# os31_master.net
KiCad netlist of a schematic drawn in EAGLE
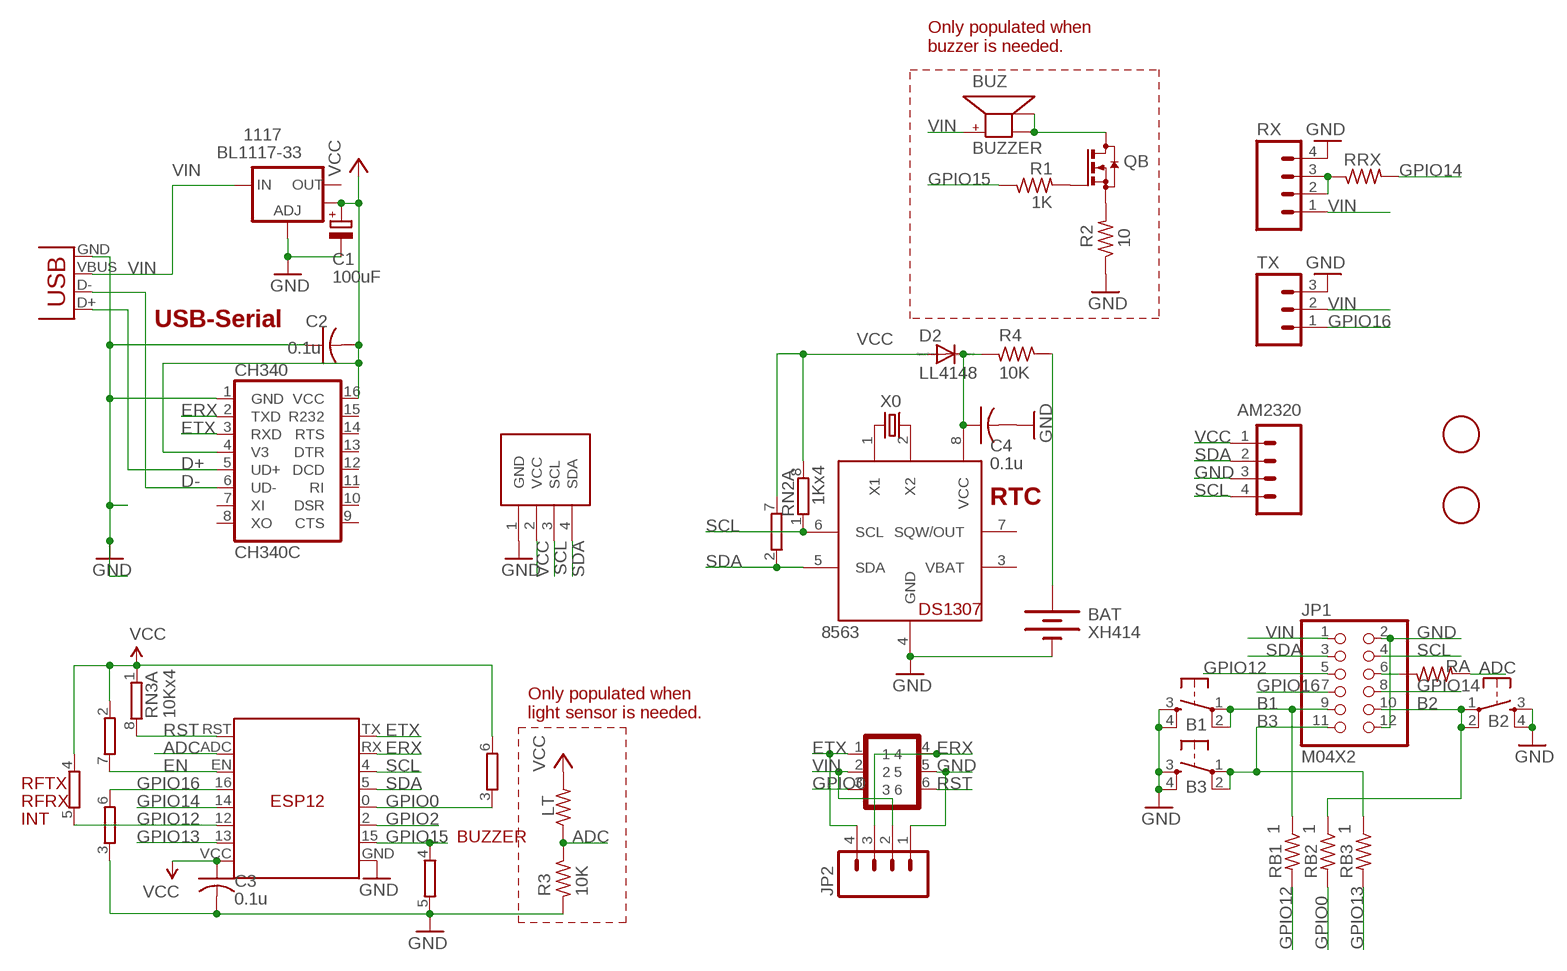
[diagram p0: schematic, sheet 1]

(export (version "E")
  (design (tool "Eeschema 10.0.6"))
  (components
    (comp (ref "1F")
      (value "FIDUCIAL")
      (footprint "eagle-import:FIDUCIAL_1MM")
      (libsource (lib "eagle-import") (part "FIDUCIAL"))
    )
    (comp (ref "2F")
      (value "FIDUCIAL")
      (footprint "eagle-import:FIDUCIAL_1MM")
      (libsource (lib "eagle-import") (part "FIDUCIAL"))
    )
    (comp (ref "1117")
      (value "BL1117-33")
      (footprint "eagle-import:SOT223")
      (libsource (lib "eagle-import") (part "V_REG_LM1117SOT223"))
    )
    (comp (ref "8563")
      (value "PCF8563")
      (footprint "eagle-import:SO08")
      (libsource (lib "eagle-import") (part "DS1307SOIC"))
    )
    (comp (ref "AM2320")
      (value "M04NARROW")
      (footprint "eagle-import:1X04-NARROW")
      (libsource (lib "eagle-import") (part "M04NARROW"))
    )
    (comp (ref "B1")
      (value "SPST_TACTEVQQ2")
      (footprint "eagle-import:EVQ-Q2")
      (libsource (lib "eagle-import") (part "SPST_TACTEVQQ2"))
    )
    (comp (ref "B2")
      (value "SPST_TACTEVQQ2")
      (footprint "eagle-import:EVQ-Q2")
      (libsource (lib "eagle-import") (part "SPST_TACTEVQQ2"))
    )
    (comp (ref "B3")
      (value "SPST_TACTEVQQ2")
      (footprint "eagle-import:EVQ-Q2")
      (libsource (lib "eagle-import") (part "SPST_TACTEVQQ2"))
    )
    (comp (ref "BAT")
      (value "XH414")
      (footprint "eagle-import:BATTCON_XH414")
      (libsource (lib "eagle-import") (part "BATTERYXH414"))
    )
    (comp (ref "BUZ")
      (value "BUZZER")
      (footprint "eagle-import:SMT-8585-BUZZER")
      (libsource (lib "eagle-import") (part "BUZZER"))
    )
    (comp (ref "C1")
      (value "100uF")
      (footprint "eagle-import:CT3528")
      (libsource (lib "eagle-import") (part "CPOL-EUCT3528"))
    )
    (comp (ref "C2")
      (value "0.1u")
      (footprint "eagle-import:C0603")
      (libsource (lib "eagle-import") (part "C-USC0603"))
    )
    (comp (ref "C3")
      (value "0.1u")
      (footprint "eagle-import:C0603")
      (libsource (lib "eagle-import") (part "C-USC0603"))
    )
    (comp (ref "C4")
      (value "0.1u")
      (footprint "eagle-import:C0603")
      (libsource (lib "eagle-import") (part "C-USC0603"))
    )
    (comp (ref "CH340")
      (value "CH340C")
      (footprint "eagle-import:SO16")
      (libsource (lib "eagle-import") (part "CH340G"))
    )
    (comp (ref "D2")
      (value "LL4148")
      (footprint "eagle-import:SOD123")
      (libsource (lib "eagle-import") (part "DIODE-SOD123"))
    )
    (comp (ref "ESP")
      (value "ESP-12N")
      (footprint "eagle-import:ESP12_WES")
      (libsource (lib "eagle-import") (part "ESP12ESPWES"))
    )
    (comp (ref "JP1")
      (value "M04X2")
      (footprint "eagle-import:2X06")
      (libsource (lib "eagle-import") (part "PINHD-2X6"))
    )
    (comp (ref "JP2")
      (value "M04PTH")
      (footprint "eagle-import:1X04")
      (libsource (lib "eagle-import") (part "SparkFunNew_M04PTH"))
    )
    (comp (ref "LCD")
      (value "SSD1306_OLED_I2CSMD3")
      (footprint "eagle-import:SSD1306_OLED_I2C_SMD3")
      (libsource (lib "eagle-import") (part "SSD1306_OLED_I2CSMD3"))
    )
    (comp (ref "LT")
      (value "100K")
      (footprint "eagle-import:R1206")
      (libsource (lib "eagle-import") (part "R-US_R1206"))
    )
    (comp (ref "QB")
      (value "MMBT3904")
      (footprint "eagle-import:SOT23")
      (libsource (lib "eagle-import") (part "BSS123"))
    )
    (comp (ref "R1")
      (value "1K")
      (footprint "eagle-import:R0603")
      (libsource (lib "eagle-import") (part "adafruitGood_R-US_R0603"))
    )
    (comp (ref "R2")
      (value "10")
      (footprint "eagle-import:R0603")
      (libsource (lib "eagle-import") (part "adafruitGood_R-US_R0603"))
    )
    (comp (ref "R3")
      (value "10K")
      (footprint "eagle-import:R0603")
      (libsource (lib "eagle-import") (part "adafruitGood_R-US_R0603"))
    )
    (comp (ref "R4")
      (value "10K")
      (footprint "eagle-import:R0603")
      (libsource (lib "eagle-import") (part "adafruitGood_R-US_R0603"))
    )
    (comp (ref "RA")
      (value "1")
      (footprint "eagle-import:R0603")
      (libsource (lib "eagle-import") (part "adafruitGood_R-US_R0603"))
    )
    (comp (ref "RB1")
      (value "1")
      (footprint "eagle-import:R0603")
      (libsource (lib "eagle-import") (part "R-US_R0603"))
    )
    (comp (ref "RB2")
      (value "1")
      (footprint "eagle-import:R0603")
      (libsource (lib "eagle-import") (part "R-US_R0603"))
    )
    (comp (ref "RB3")
      (value "1")
      (footprint "eagle-import:R0603")
      (libsource (lib "eagle-import") (part "R-US_R0603"))
    )
    (comp (ref "RN2")
      (value "1Kx4")
      (footprint "eagle-import:EXB38V")
      (libsource (lib "eagle-import") (part "4R-NEXB38V"))
    )
    (comp (ref "RN3")
      (value "10Kx4")
      (footprint "eagle-import:EXB38V")
      (libsource (lib "eagle-import") (part "4R-NEXB38V"))
    )
    (comp (ref "RRX")
      (value "1K")
      (footprint "eagle-import:R0603")
      (libsource (lib "eagle-import") (part "adafruitGood_R-US_R0603"))
    )
    (comp (ref "RX")
      (value "M04LOCK")
      (footprint "eagle-import:1X04_LOCK")
      (libsource (lib "eagle-import") (part "M04LOCK"))
    )
    (comp (ref "TX")
      (value "M03LOCK")
      (footprint "eagle-import:1X03_LOCK")
      (libsource (lib "eagle-import") (part "M03LOCK"))
    )
    (comp (ref "U$3")
      (value "GOLDFINGER_2X3")
      (footprint "eagle-import:GOLDFINGER_2X3")
      (libsource (lib "eagle-import") (part "GOLDFINGER_2X3"))
    )
    (comp (ref "USB")
      (value "USBMICROB2")
      (footprint "eagle-import:USB-MICROB2")
      (libsource (lib "eagle-import") (part "USBMICROB2"))
    )
    (comp (ref "X0")
      (value "32.768kHz")
      (footprint "eagle-import:MM20SS1")
      (libsource (lib "eagle-import") (part "CRYSTALMM20SS1"))
    )
  )
  (nets
    (net (code "1") (name "/ADC") (class "Default")
      (node (ref "ESP") (pin "ADC") (pinfunction "ADC_ADC") (pintype "bidirectional"))
      (node (ref "LT") (pin "1") (pinfunction "1_1") (pintype "passive"))
      (node (ref "R3") (pin "1") (pinfunction "1_1") (pintype "passive"))
      (node (ref "RA") (pin "2") (pinfunction "2_2") (pintype "passive"))
    )
    (net (code "2") (name "/B1") (class "Default")
      (node (ref "B1") (pin "1") (pinfunction "1_1") (pintype "passive"))
      (node (ref "B1") (pin "2") (pinfunction "2_2") (pintype "passive"))
      (node (ref "JP1") (pin "9") (pinfunction "9_9") (pintype "passive"))
      (node (ref "RB1") (pin "1") (pinfunction "1_1") (pintype "passive"))
    )
    (net (code "3") (name "/B2") (class "Default")
      (node (ref "B2") (pin "1") (pinfunction "1_1") (pintype "passive"))
      (node (ref "B2") (pin "2") (pinfunction "2_2") (pintype "passive"))
      (node (ref "JP1") (pin "10") (pinfunction "10_10") (pintype "passive"))
      (node (ref "RB2") (pin "1") (pinfunction "1_1") (pintype "passive"))
    )
    (net (code "4") (name "/B3") (class "Default")
      (node (ref "B3") (pin "1") (pinfunction "1_1") (pintype "passive"))
      (node (ref "B3") (pin "2") (pinfunction "2_2") (pintype "passive"))
      (node (ref "JP1") (pin "11") (pinfunction "11_11") (pintype "passive"))
      (node (ref "RB3") (pin "1") (pinfunction "1_1") (pintype "passive"))
    )
    (net (code "5") (name "/D+") (class "Default")
      (node (ref "CH340") (pin "5") (pinfunction "UD+_5") (pintype "bidirectional"))
      (node (ref "USB") (pin "D+") (pinfunction "D+_D+") (pintype "bidirectional"))
    )
    (net (code "6") (name "/D-") (class "Default")
      (node (ref "CH340") (pin "6") (pinfunction "UD-_6") (pintype "bidirectional"))
      (node (ref "USB") (pin "D-") (pinfunction "D-_D-") (pintype "bidirectional"))
    )
    (net (code "7") (name "/EN") (class "Default")
      (node (ref "ESP") (pin "EN") (pinfunction "EN_EN") (pintype "bidirectional"))
      (node (ref "RN3") (pin "7") (pinfunction "2_7") (pintype "passive"))
    )
    (net (code "8") (name "/ERX") (class "Default")
      (node (ref "CH340") (pin "2") (pinfunction "TXD_2") (pintype "bidirectional"))
      (node (ref "ESP") (pin "RX") (pinfunction "RX_RX") (pintype "bidirectional"))
      (node (ref "JP2") (pin "3") (pinfunction "3_3") (pintype "passive"))
      (node (ref "U$3") (pin "4") (pinfunction "4_4") (pintype "bidirectional"))
    )
    (net (code "9") (name "/ETX") (class "Default")
      (node (ref "CH340") (pin "3") (pinfunction "RXD_3") (pintype "bidirectional"))
      (node (ref "ESP") (pin "TX") (pinfunction "TX_TX") (pintype "bidirectional"))
      (node (ref "JP2") (pin "4") (pinfunction "4_4") (pintype "passive"))
      (node (ref "U$3") (pin "1") (pinfunction "1_1") (pintype "bidirectional"))
    )
    (net (code "10") (name "/GPIO0") (class "Default")
      (node (ref "ESP") (pin "0") (pinfunction "G0_0") (pintype "bidirectional"))
      (node (ref "RB2") (pin "2") (pinfunction "2_2") (pintype "passive"))
      (node (ref "RN2") (pin "3") (pinfunction "1_3") (pintype "passive"))
      (node (ref "U$3") (pin "3") (pinfunction "3_3") (pintype "bidirectional"))
    )
    (net (code "11") (name "/GPIO2") (class "Default")
      (node (ref "ESP") (pin "2") (pinfunction "G2_2") (pintype "bidirectional"))
    )
    (net (code "12") (name "/GPIO12") (class "Default")
      (node (ref "ESP") (pin "12") (pinfunction "G12_12") (pintype "bidirectional"))
      (node (ref "JP1") (pin "5") (pinfunction "5_5") (pintype "passive"))
      (node (ref "RB1") (pin "2") (pinfunction "2_2") (pintype "passive"))
      (node (ref "RN3") (pin "5") (pinfunction "2_5") (pintype "passive"))
    )
    (net (code "13") (name "/GPIO13") (class "Default")
      (node (ref "ESP") (pin "13") (pinfunction "G13_13") (pintype "bidirectional"))
      (node (ref "RB3") (pin "2") (pinfunction "2_2") (pintype "passive"))
    )
    (net (code "14") (name "/GPIO14") (class "Default")
      (node (ref "ESP") (pin "14") (pinfunction "G14_14") (pintype "bidirectional"))
      (node (ref "JP1") (pin "8") (pinfunction "8_8") (pintype "passive"))
      (node (ref "RRX") (pin "2") (pinfunction "2_2") (pintype "passive"))
    )
    (net (code "15") (name "/GPIO15") (class "Default")
      (node (ref "ESP") (pin "15") (pinfunction "G15_15") (pintype "bidirectional"))
      (node (ref "R1") (pin "1") (pinfunction "1_1") (pintype "passive"))
      (node (ref "RN2") (pin "4") (pinfunction "1_4") (pintype "passive"))
    )
    (net (code "16") (name "/GPIO16") (class "Default")
      (node (ref "ESP") (pin "16") (pinfunction "G16_16") (pintype "bidirectional"))
      (node (ref "JP1") (pin "7") (pinfunction "7_7") (pintype "passive"))
      (node (ref "RN3") (pin "6") (pinfunction "2_6") (pintype "passive"))
      (node (ref "TX") (pin "1") (pinfunction "1_1") (pintype "passive"))
    )
    (net (code "17") (name "/RST") (class "Default")
      (node (ref "ESP") (pin "RST") (pinfunction "RST_RST") (pintype "bidirectional"))
      (node (ref "RN3") (pin "8") (pinfunction "2_8") (pintype "passive"))
      (node (ref "U$3") (pin "6") (pinfunction "6_6") (pintype "bidirectional"))
    )
    (net (code "18") (name "/SCL") (class "Default")
      (node (ref "8563") (pin "6") (pinfunction "SCL_6") (pintype "bidirectional"))
      (node (ref "AM2320") (pin "4") (pinfunction "4_4") (pintype "passive"))
      (node (ref "ESP") (pin "4") (pinfunction "G4_4") (pintype "bidirectional"))
      (node (ref "JP1") (pin "4") (pinfunction "4_4") (pintype "passive"))
      (node (ref "LCD") (pin "3") (pinfunction "SCL_3") (pintype "bidirectional"))
      (node (ref "RN2") (pin "1") (pinfunction "1_1") (pintype "passive"))
    )
    (net (code "19") (name "/SDA") (class "Default")
      (node (ref "8563") (pin "5") (pinfunction "SDA_5") (pintype "bidirectional"))
      (node (ref "AM2320") (pin "2") (pinfunction "2_2") (pintype "passive"))
      (node (ref "ESP") (pin "5") (pinfunction "G5_5") (pintype "bidirectional"))
      (node (ref "JP1") (pin "3") (pinfunction "3_3") (pintype "passive"))
      (node (ref "LCD") (pin "4") (pinfunction "SDA_4") (pintype "bidirectional"))
      (node (ref "RN2") (pin "2") (pinfunction "1_2") (pintype "passive"))
    )
    (net (code "20") (name "/VBAT") (class "Default")
      (node (ref "8563") (pin "3") (pinfunction "VBAT_3") (pintype "power_in"))
    )
    (net (code "21") (name "/VIN") (class "Default")
      (node (ref "1117") (pin "3") (pinfunction "IN_3") (pintype "input"))
      (node (ref "BUZ") (pin "+") (pinfunction "+_+") (pintype "passive"))
      (node (ref "JP1") (pin "1") (pinfunction "1_1") (pintype "passive"))
      (node (ref "JP2") (pin "2") (pinfunction "2_2") (pintype "passive"))
      (node (ref "RX") (pin "1") (pinfunction "1_1") (pintype "passive"))
      (node (ref "TX") (pin "2") (pinfunction "2_2") (pintype "passive"))
      (node (ref "U$3") (pin "2") (pinfunction "2_2") (pintype "bidirectional"))
      (node (ref "USB") (pin "VBUS") (pinfunction "VBUS_VBUS") (pintype "bidirectional"))
    )
    (net (code "22") (name "GND") (class "Default")
      (node (ref "1117") (pin "1") (pinfunction "ADJ_1") (pintype "input"))
      (node (ref "8563") (pin "4") (pinfunction "GND_4") (pintype "power_in"))
      (node (ref "AM2320") (pin "3") (pinfunction "3_3") (pintype "passive"))
      (node (ref "B1") (pin "3") (pinfunction "3_3") (pintype "passive"))
      (node (ref "B1") (pin "4") (pinfunction "4_4") (pintype "passive"))
      (node (ref "B2") (pin "3") (pinfunction "3_3") (pintype "passive"))
      (node (ref "B2") (pin "4") (pinfunction "4_4") (pintype "passive"))
      (node (ref "B3") (pin "3") (pinfunction "3_3") (pintype "passive"))
      (node (ref "B3") (pin "4") (pinfunction "4_4") (pintype "passive"))
      (node (ref "BAT") (pin "P$1") (pinfunction "-_P$1") (pintype "power_in"))
      (node (ref "C1") (pin "+") (pinfunction "-_+") (pintype "passive"))
      (node (ref "C2") (pin "1") (pinfunction "1_1") (pintype "passive"))
      (node (ref "C3") (pin "2") (pinfunction "2_2") (pintype "passive"))
      (node (ref "C4") (pin "2") (pinfunction "2_2") (pintype "passive"))
      (node (ref "CH340") (pin "1") (pinfunction "GND_1") (pintype "power_in"))
      (node (ref "ESP") (pin "GND") (pinfunction "GND_GND") (pintype "power_in"))
      (node (ref "JP1") (pin "12") (pinfunction "12_12") (pintype "passive"))
      (node (ref "JP1") (pin "2") (pinfunction "2_2") (pintype "passive"))
      (node (ref "JP2") (pin "1") (pinfunction "1_1") (pintype "passive"))
      (node (ref "LCD") (pin "1") (pinfunction "GND_1") (pintype "power_in"))
      (node (ref "R2") (pin "1") (pinfunction "1_1") (pintype "passive"))
      (node (ref "R3") (pin "2") (pinfunction "2_2") (pintype "passive"))
      (node (ref "RN2") (pin "5") (pinfunction "2_5") (pintype "passive"))
      (node (ref "RN3") (pin "3") (pinfunction "1_3") (pintype "passive"))
      (node (ref "RX") (pin "4") (pinfunction "4_4") (pintype "passive"))
      (node (ref "TX") (pin "3") (pinfunction "3_3") (pintype "passive"))
      (node (ref "U$3") (pin "5") (pinfunction "5_5") (pintype "bidirectional"))
      (node (ref "USB") (pin "GND") (pinfunction "GND_GND") (pintype "bidirectional"))
    )
    (net (code "23") (name "Net-(8563-VCC)") (class "Default")
      (node (ref "8563") (pin "8") (pinfunction "VCC_8") (pintype "power_in"))
      (node (ref "C4") (pin "1") (pinfunction "1_1") (pintype "passive"))
      (node (ref "D2") (pin "C") (pinfunction "C_C") (pintype "passive"))
      (node (ref "R4") (pin "2") (pinfunction "2_2") (pintype "passive"))
    )
    (net (code "24") (name "Net-(8563-X1)") (class "Default")
      (node (ref "8563") (pin "1") (pinfunction "X1_1") (pintype "passive"))
      (node (ref "X0") (pin "1") (pinfunction "1_1") (pintype "passive"))
    )
    (net (code "25") (name "Net-(8563-X2)") (class "Default")
      (node (ref "8563") (pin "2") (pinfunction "X2_2") (pintype "passive"))
      (node (ref "X0") (pin "4") (pinfunction "2_4") (pintype "passive"))
    )
    (net (code "26") (name "Net-(BAT-+)") (class "Default")
      (node (ref "BAT") (pin "P$2") (pinfunction "+_P$2") (pintype "power_in"))
      (node (ref "R4") (pin "1") (pinfunction "1_1") (pintype "passive"))
    )
    (net (code "27") (name "Net-(JP1-Pad6)") (class "Default")
      (node (ref "JP1") (pin "6") (pinfunction "6_6") (pintype "passive"))
      (node (ref "RA") (pin "1") (pinfunction "1_1") (pintype "passive"))
    )
    (net (code "28") (name "Net-(QB-D)") (class "Default")
      (node (ref "BUZ") (pin "-") (pinfunction "-_-") (pintype "passive"))
      (node (ref "BUZ") (pin "A-") (pinfunction "A-_A-") (pintype "passive"))
      (node (ref "QB") (pin "3") (pinfunction "D_3") (pintype "passive"))
    )
    (net (code "29") (name "Net-(QB-G)") (class "Default")
      (node (ref "QB") (pin "1") (pinfunction "G_1") (pintype "passive"))
      (node (ref "R1") (pin "2") (pinfunction "2_2") (pintype "passive"))
    )
    (net (code "30") (name "Net-(QB-S)") (class "Default")
      (node (ref "QB") (pin "2") (pinfunction "S_2") (pintype "passive"))
      (node (ref "R2") (pin "2") (pinfunction "2_2") (pintype "passive"))
    )
    (net (code "31") (name "Net-(RRX-Pad1)") (class "Default")
      (node (ref "RRX") (pin "1") (pinfunction "1_1") (pintype "passive"))
      (node (ref "RX") (pin "2") (pinfunction "2_2") (pintype "passive"))
      (node (ref "RX") (pin "3") (pinfunction "3_3") (pintype "passive"))
    )
    (net (code "32") (name "VCC") (class "Default")
      (node (ref "1117") (pin "4") (pinfunction "OUT_4") (pintype "bidirectional"))
      (node (ref "AM2320") (pin "1") (pinfunction "1_1") (pintype "passive"))
      (node (ref "C1") (pin "-") (pinfunction "+_-") (pintype "passive"))
      (node (ref "C2") (pin "2") (pinfunction "2_2") (pintype "passive"))
      (node (ref "C3") (pin "1") (pinfunction "1_1") (pintype "passive"))
      (node (ref "CH340") (pin "16") (pinfunction "VCC_16") (pintype "power_in"))
      (node (ref "CH340") (pin "4") (pinfunction "V3_4") (pintype "bidirectional"))
      (node (ref "D2") (pin "A") (pinfunction "A_A") (pintype "passive"))
      (node (ref "ESP") (pin "VCC") (pinfunction "VCC_VCC") (pintype "power_in"))
      (node (ref "LCD") (pin "2") (pinfunction "VCC_2") (pintype "power_in"))
      (node (ref "LT") (pin "2") (pinfunction "2_2") (pintype "passive"))
      (node (ref "RN2") (pin "6") (pinfunction "2_6") (pintype "passive"))
      (node (ref "RN2") (pin "7") (pinfunction "2_7") (pintype "passive"))
      (node (ref "RN2") (pin "8") (pinfunction "2_8") (pintype "passive"))
      (node (ref "RN3") (pin "1") (pinfunction "1_1") (pintype "passive"))
      (node (ref "RN3") (pin "2") (pinfunction "1_2") (pintype "passive"))
      (node (ref "RN3") (pin "4") (pinfunction "1_4") (pintype "passive"))
    )
    (net (code "33") (name "unconnected-(1117-OUT-Pad2)") (class "Default")
      (node (ref "1117") (pin "2") (pinfunction "OUT_2") (pintype "bidirectional"))
    )
    (net (code "34") (name "unconnected-(8563-SQW{slash}OUT-Pad7)") (class "Default")
      (node (ref "8563") (pin "7") (pinfunction "SQW/OUT_7") (pintype "bidirectional"))
    )
    (net (code "35") (name "unconnected-(CH340-CTS-Pad9)") (class "Default")
      (node (ref "CH340") (pin "9") (pinfunction "CTS_9") (pintype "bidirectional"))
    )
    (net (code "36") (name "unconnected-(CH340-DCD-Pad12)") (class "Default")
      (node (ref "CH340") (pin "12") (pinfunction "DCD_12") (pintype "bidirectional"))
    )
    (net (code "37") (name "unconnected-(CH340-DSR-Pad10)") (class "Default")
      (node (ref "CH340") (pin "10") (pinfunction "DSR_10") (pintype "bidirectional"))
    )
    (net (code "38") (name "unconnected-(CH340-DTR-Pad13)") (class "Default")
      (node (ref "CH340") (pin "13") (pinfunction "DTR_13") (pintype "bidirectional"))
    )
    (net (code "39") (name "unconnected-(CH340-R232-Pad15)") (class "Default")
      (node (ref "CH340") (pin "15") (pinfunction "R232_15") (pintype "bidirectional"))
    )
    (net (code "40") (name "unconnected-(CH340-RI-Pad11)") (class "Default")
      (node (ref "CH340") (pin "11") (pinfunction "RI_11") (pintype "bidirectional"))
    )
    (net (code "41") (name "unconnected-(CH340-RTS-Pad14)") (class "Default")
      (node (ref "CH340") (pin "14") (pinfunction "RTS_14") (pintype "bidirectional"))
    )
    (net (code "42") (name "unconnected-(CH340-XI-Pad7)") (class "Default")
      (node (ref "CH340") (pin "7") (pinfunction "XI_7") (pintype "bidirectional"))
    )
    (net (code "43") (name "unconnected-(CH340-XO-Pad8)") (class "Default")
      (node (ref "CH340") (pin "8") (pinfunction "XO_8") (pintype "bidirectional"))
    )
  )
)
